# omaha_final.net
KiCad netlist of a schematic drawn in EAGLE
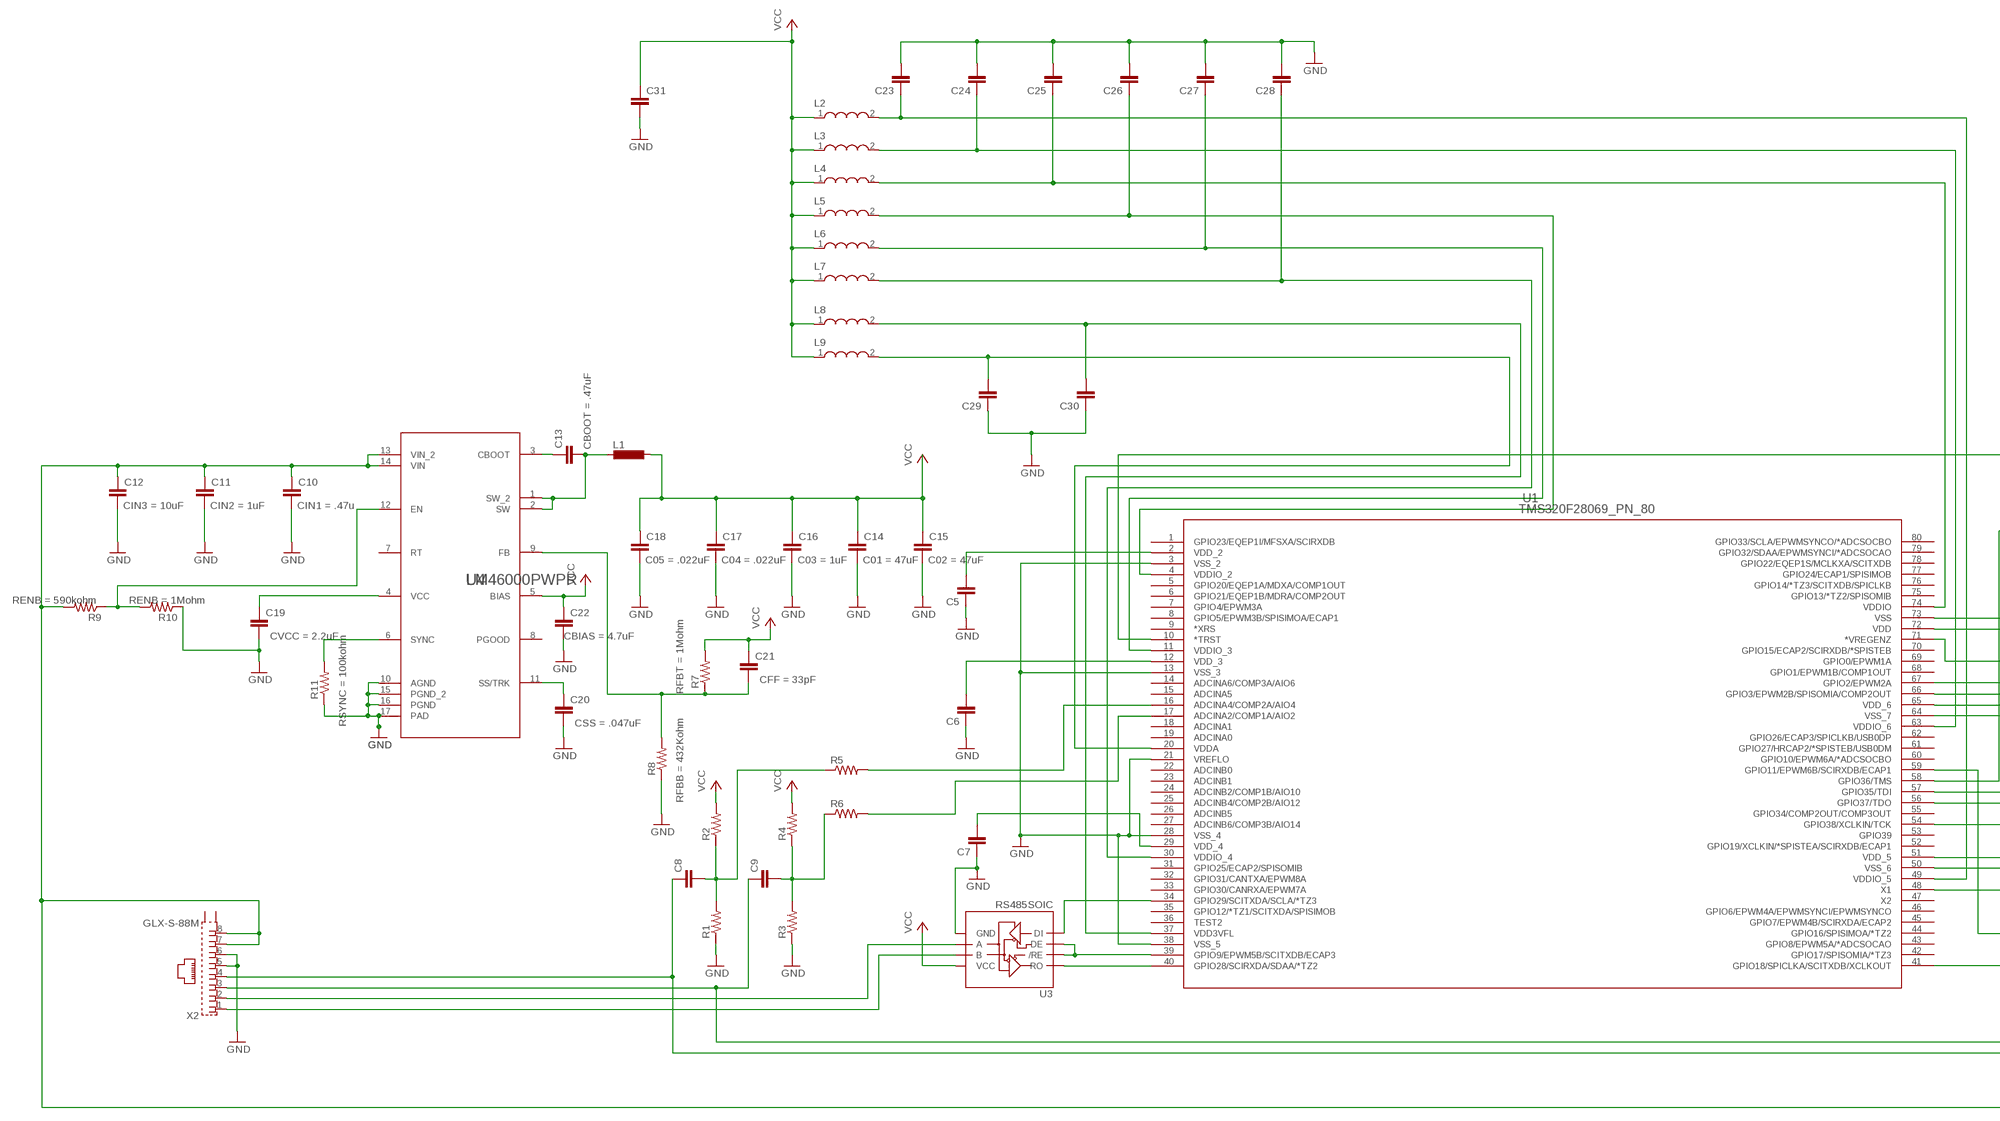
[diagram p0: schematic, sheet 1, part 1 of 2]
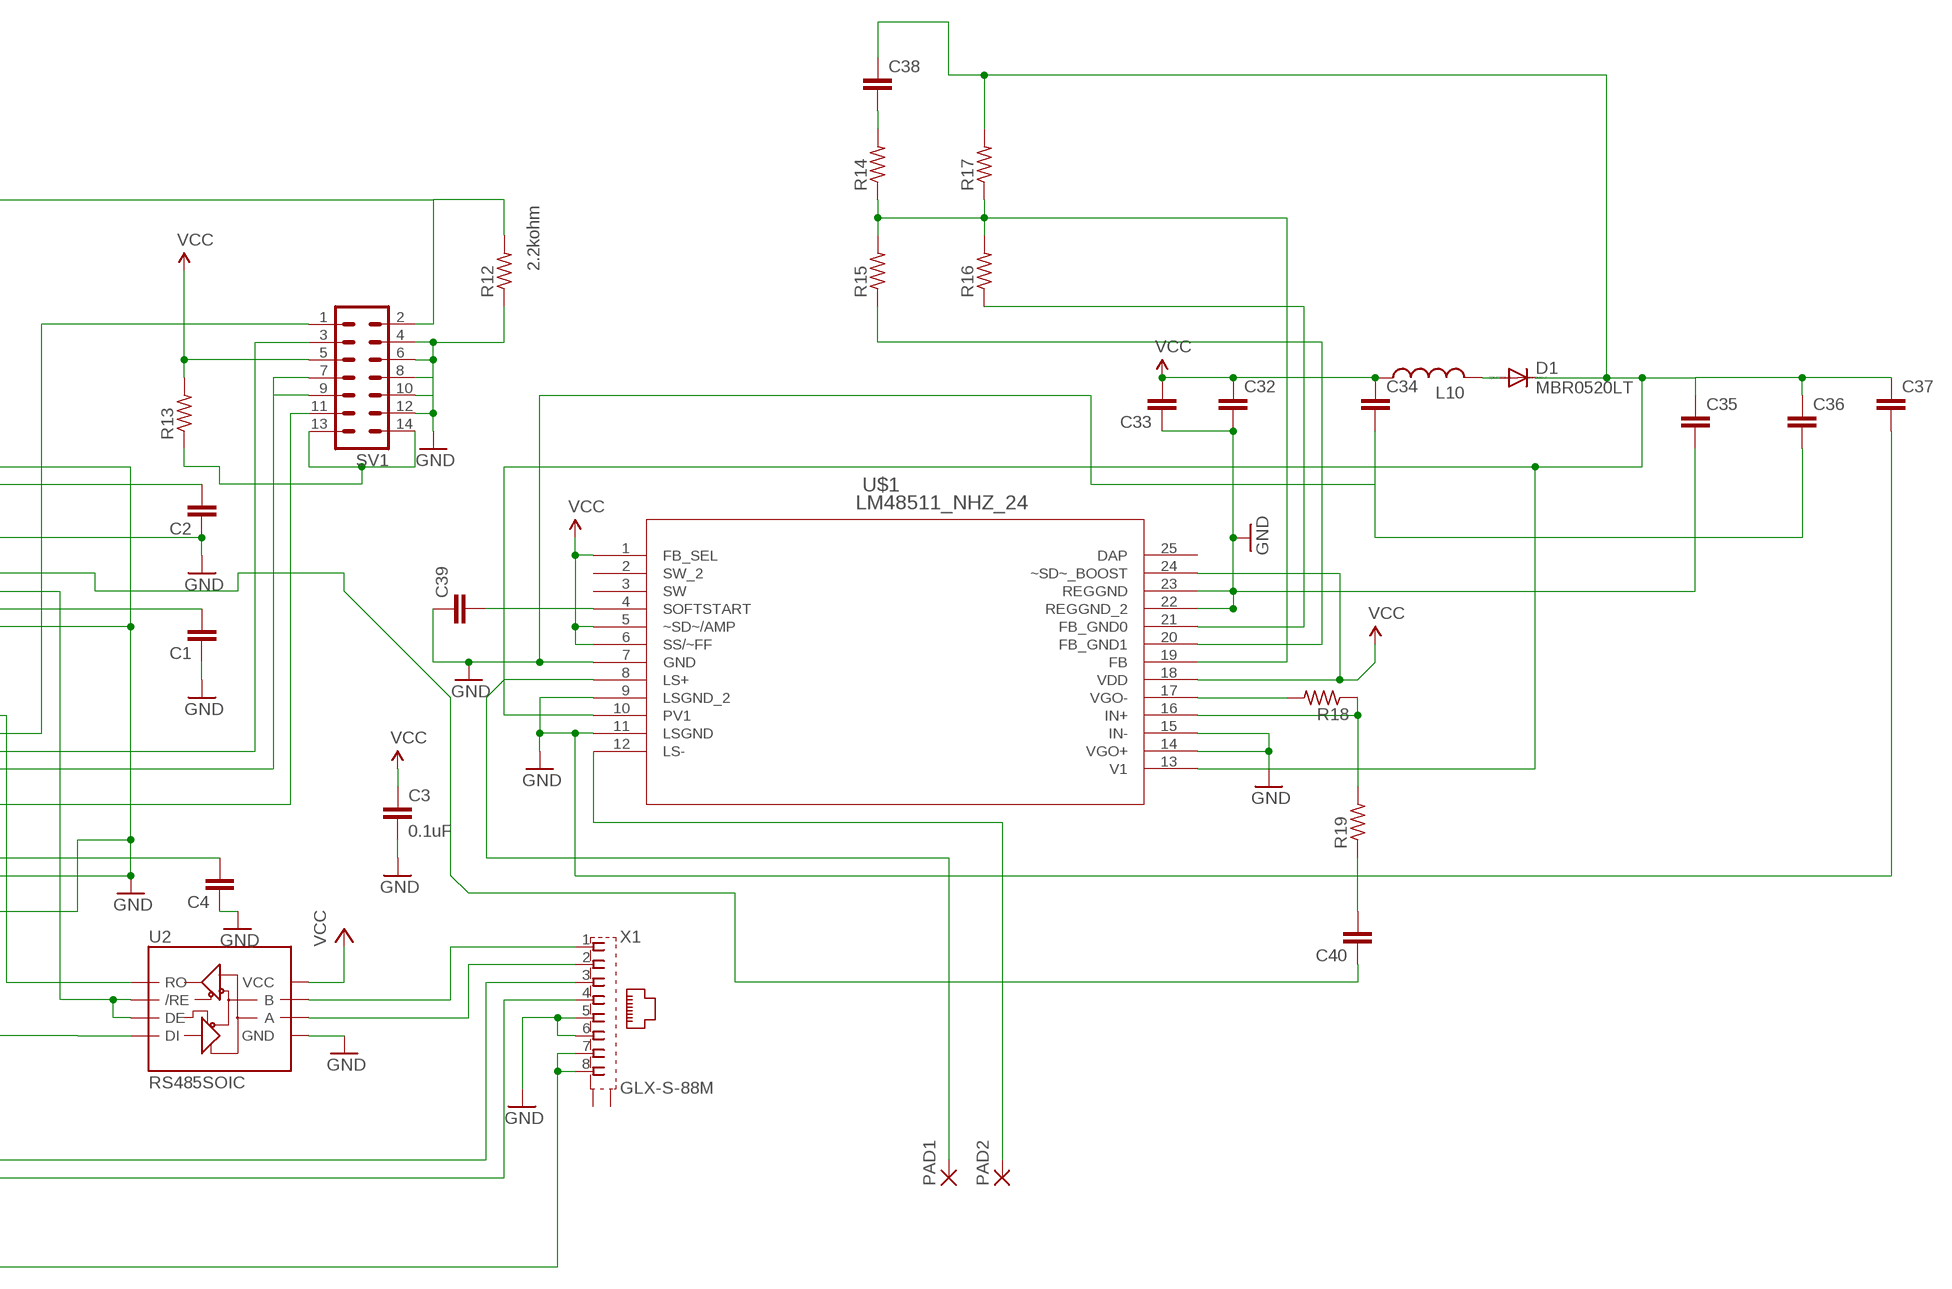
[diagram p1: schematic, sheet 1, part 2 of 2]

(export (version "E")
  (design (tool "Eeschema 10.0.6"))
  (components
    (comp (ref "C1")
      (value "C-EUC0603")
      (footprint "eagle-import:C0603")
      (libsource (lib "eagle-import") (part "C-EUC0603"))
    )
    (comp (ref "C2")
      (value "C-EUC0603")
      (footprint "eagle-import:C0603")
      (libsource (lib "eagle-import") (part "C-EUC0603"))
    )
    (comp (ref "C3")
      (value "0.1uF")
      (footprint "eagle-import:0603-CAP")
      (libsource (lib "eagle-import") (part "0.1UF-25V(+80/-20%)(0603)"))
    )
    (comp (ref "C4")
      (value "C-EUC0603")
      (footprint "eagle-import:C0603")
      (libsource (lib "eagle-import") (part "C-EUC0603"))
    )
    (comp (ref "C5")
      (value "C-EUC0603")
      (footprint "eagle-import:C0603")
      (libsource (lib "eagle-import") (part "C-EUC0603"))
    )
    (comp (ref "C6")
      (value "C-EUC0603")
      (footprint "eagle-import:C0603")
      (libsource (lib "eagle-import") (part "C-EUC0603"))
    )
    (comp (ref "C7")
      (value "C-EUC0603")
      (footprint "eagle-import:C0603")
      (libsource (lib "eagle-import") (part "C-EUC0603"))
    )
    (comp (ref "C8")
      (value "C-EUC0603")
      (footprint "eagle-import:C0603")
      (libsource (lib "eagle-import") (part "C-EUC0603"))
    )
    (comp (ref "C9")
      (value "C-EUC0603")
      (footprint "eagle-import:C0603")
      (libsource (lib "eagle-import") (part "C-EUC0603"))
    )
    (comp (ref "C10")
      (value "C-EUC0805")
      (footprint "eagle-import:C0805")
      (fields (field (name "CIN1") ".47u"))
      (libsource (lib "eagle-import") (part "C-EUC0805"))
    )
    (comp (ref "C11")
      (value "C-EUC1210")
      (footprint "eagle-import:C1210")
      (fields (field (name "CIN2") "1uF"))
      (libsource (lib "eagle-import") (part "C-EUC1210"))
    )
    (comp (ref "C12")
      (value "C-EUC2220K")
      (footprint "eagle-import:C2220K")
      (fields (field (name "CIN3") "10uF"))
      (libsource (lib "eagle-import") (part "C-EUC2220K"))
    )
    (comp (ref "C13")
      (value "C-EUC0805")
      (footprint "eagle-import:C0805")
      (fields (field (name "CBOOT") ".47uF"))
      (libsource (lib "eagle-import") (part "C-EUC0805"))
    )
    (comp (ref "C14")
      (value "C-EUC1210")
      (footprint "eagle-import:C1210")
      (fields (field (name "C01") "47uF"))
      (libsource (lib "eagle-import") (part "C-EUC1210"))
    )
    (comp (ref "C15")
      (value "C-EUC1210")
      (footprint "eagle-import:C1210")
      (fields (field (name "C02") "47uF"))
      (libsource (lib "eagle-import") (part "C-EUC1210"))
    )
    (comp (ref "C16")
      (value "C-EUC0805")
      (footprint "eagle-import:C0805")
      (fields (field (name "C03") "1uF"))
      (libsource (lib "eagle-import") (part "C-EUC0805"))
    )
    (comp (ref "C17")
      (value "C-EUC0805")
      (footprint "eagle-import:C0805")
      (fields (field (name "C04") ".022uF"))
      (libsource (lib "eagle-import") (part "C-EUC0805"))
    )
    (comp (ref "C18")
      (value "C-EUC0805")
      (footprint "eagle-import:C0805")
      (fields (field (name "C05") ".022uF"))
      (libsource (lib "eagle-import") (part "C-EUC0805"))
    )
    (comp (ref "C19")
      (value "C-EUC0603")
      (footprint "eagle-import:C0603")
      (fields (field (name "CVCC") "2.2uF"))
      (libsource (lib "eagle-import") (part "C-EUC0603"))
    )
    (comp (ref "C20")
      (value "C-EUC0603")
      (footprint "eagle-import:C0603")
      (fields (field (name "CSS") ".047uF"))
      (libsource (lib "eagle-import") (part "C-EUC0603"))
    )
    (comp (ref "C21")
      (value "C-EUC0603")
      (footprint "eagle-import:C0603")
      (fields (field (name "CFF") "33pF"))
      (libsource (lib "eagle-import") (part "C-EUC0603"))
    )
    (comp (ref "C22")
      (value "C-EUC0805")
      (footprint "eagle-import:C0805")
      (fields (field (name "CBIAS") "4.7uF"))
      (libsource (lib "eagle-import") (part "C-EUC0805"))
    )
    (comp (ref "C23")
      (value "C-EUC0603")
      (footprint "eagle-import:C0603")
      (libsource (lib "eagle-import") (part "C-EUC0603"))
    )
    (comp (ref "C24")
      (value "C-EUC0603")
      (footprint "eagle-import:C0603")
      (libsource (lib "eagle-import") (part "C-EUC0603"))
    )
    (comp (ref "C25")
      (value "C-EUC0603")
      (footprint "eagle-import:C0603")
      (libsource (lib "eagle-import") (part "C-EUC0603"))
    )
    (comp (ref "C26")
      (value "C-EUC0603")
      (footprint "eagle-import:C0603")
      (libsource (lib "eagle-import") (part "C-EUC0603"))
    )
    (comp (ref "C27")
      (value "C-EUC0603")
      (footprint "eagle-import:C0603")
      (libsource (lib "eagle-import") (part "C-EUC0603"))
    )
    (comp (ref "C28")
      (value "C-EUC0603")
      (footprint "eagle-import:C0603")
      (libsource (lib "eagle-import") (part "C-EUC0603"))
    )
    (comp (ref "C29")
      (value "C-EUC0603")
      (footprint "eagle-import:C0603")
      (libsource (lib "eagle-import") (part "C-EUC0603"))
    )
    (comp (ref "C30")
      (value "C-EUC0603")
      (footprint "eagle-import:C0603")
      (libsource (lib "eagle-import") (part "C-EUC0603"))
    )
    (comp (ref "C31")
      (value "C-EUC0603")
      (footprint "eagle-import:C0603")
      (libsource (lib "eagle-import") (part "C-EUC0603"))
    )
    (comp (ref "C32")
      (value "C-EUC0805")
      (footprint "eagle-import:C0805")
      (libsource (lib "eagle-import") (part "C-EUC0805"))
    )
    (comp (ref "C33")
      (value "C-EUC0805")
      (footprint "eagle-import:C0805")
      (libsource (lib "eagle-import") (part "C-EUC0805"))
    )
    (comp (ref "C34")
      (value "C-EUC0805")
      (footprint "eagle-import:C0805")
      (libsource (lib "eagle-import") (part "C-EUC0805"))
    )
    (comp (ref "C35")
      (value "C-EUC0805")
      (footprint "eagle-import:C0805")
      (libsource (lib "eagle-import") (part "C-EUC0805"))
    )
    (comp (ref "C36")
      (value "C-EUC0805")
      (footprint "eagle-import:C0805")
      (libsource (lib "eagle-import") (part "C-EUC0805"))
    )
    (comp (ref "C37")
      (value "C-EUC0805")
      (footprint "eagle-import:C0805")
      (libsource (lib "eagle-import") (part "C-EUC0805"))
    )
    (comp (ref "C38")
      (value "C-EUC0805")
      (footprint "eagle-import:C0805")
      (libsource (lib "eagle-import") (part "C-EUC0805"))
    )
    (comp (ref "C39")
      (value "C-EUC0805")
      (footprint "eagle-import:C0805")
      (libsource (lib "eagle-import") (part "C-EUC0805"))
    )
    (comp (ref "C40")
      (value "C-EUC0805")
      (footprint "eagle-import:C0805")
      (libsource (lib "eagle-import") (part "C-EUC0805"))
    )
    (comp (ref "D1")
      (value "MBR0520LT")
      (footprint "eagle-import:SOD123")
      (libsource (lib "eagle-import") (part "MBR0520LT"))
    )
    (comp (ref "L1")
      (value "DO3316P")
      (footprint "eagle-import:DO3316P")
      (libsource (lib "eagle-import") (part "DO3316P"))
    )
    (comp (ref "L2")
      (value "WE-KI_0805A")
      (footprint "eagle-import:WE-KI_0805A")
      (libsource (lib "eagle-import") (part "WE-KI_0805A"))
    )
    (comp (ref "L3")
      (value "WE-KI_0805A")
      (footprint "eagle-import:WE-KI_0805A")
      (libsource (lib "eagle-import") (part "WE-KI_0805A"))
    )
    (comp (ref "L4")
      (value "WE-KI_0805A")
      (footprint "eagle-import:WE-KI_0805A")
      (libsource (lib "eagle-import") (part "WE-KI_0805A"))
    )
    (comp (ref "L5")
      (value "WE-KI_0805A")
      (footprint "eagle-import:WE-KI_0805A")
      (libsource (lib "eagle-import") (part "WE-KI_0805A"))
    )
    (comp (ref "L6")
      (value "WE-KI_0805A")
      (footprint "eagle-import:WE-KI_0805A")
      (libsource (lib "eagle-import") (part "WE-KI_0805A"))
    )
    (comp (ref "L7")
      (value "WE-KI_0805A")
      (footprint "eagle-import:WE-KI_0805A")
      (libsource (lib "eagle-import") (part "WE-KI_0805A"))
    )
    (comp (ref "L8")
      (value "WE-KI_0805A")
      (footprint "eagle-import:WE-KI_0805A")
      (libsource (lib "eagle-import") (part "WE-KI_0805A"))
    )
    (comp (ref "L9")
      (value "WE-KI_0805A")
      (footprint "eagle-import:WE-KI_0805A")
      (libsource (lib "eagle-import") (part "WE-KI_0805A"))
    )
    (comp (ref "L10")
      (value "L-USL5650M")
      (footprint "eagle-import:L5650M")
      (libsource (lib "eagle-import") (part "L-USL5650M"))
    )
    (comp (ref "PAD1")
      (value "3,81/1,4")
      (footprint "eagle-import:3,81_1,4")
      (libsource (lib "eagle-import") (part "3,81/1,4"))
    )
    (comp (ref "PAD2")
      (value "3,81/1,4")
      (footprint "eagle-import:3,81_1,4")
      (libsource (lib "eagle-import") (part "3,81/1,4"))
    )
    (comp (ref "R1")
      (value "R-US_R0603")
      (footprint "eagle-import:R0603")
      (libsource (lib "eagle-import") (part "R-US_R0603"))
    )
    (comp (ref "R2")
      (value "R-US_R0603")
      (footprint "eagle-import:R0603")
      (libsource (lib "eagle-import") (part "R-US_R0603"))
    )
    (comp (ref "R3")
      (value "R-US_R0603")
      (footprint "eagle-import:R0603")
      (libsource (lib "eagle-import") (part "R-US_R0603"))
    )
    (comp (ref "R4")
      (value "R-US_R0603")
      (footprint "eagle-import:R0603")
      (libsource (lib "eagle-import") (part "R-US_R0603"))
    )
    (comp (ref "R5")
      (value "R-US_R0603")
      (footprint "eagle-import:R0603")
      (libsource (lib "eagle-import") (part "R-US_R0603"))
    )
    (comp (ref "R6")
      (value "R-US_R0603")
      (footprint "eagle-import:R0603")
      (libsource (lib "eagle-import") (part "R-US_R0603"))
    )
    (comp (ref "R7")
      (value "R-US_R0603")
      (footprint "eagle-import:R0603")
      (fields (field (name "RFBT") "1Mohm"))
      (libsource (lib "eagle-import") (part "R-US_R0603"))
    )
    (comp (ref "R8")
      (value "R-US_R0603")
      (footprint "eagle-import:R0603")
      (fields (field (name "RFBB") "432Kohm"))
      (libsource (lib "eagle-import") (part "R-US_R0603"))
    )
    (comp (ref "R9")
      (value "R-US_R0603")
      (footprint "eagle-import:R0603")
      (fields (field (name "RENB") "590kohm"))
      (libsource (lib "eagle-import") (part "R-US_R0603"))
    )
    (comp (ref "R10")
      (value "R-US_R0603")
      (footprint "eagle-import:R0603")
      (fields (field (name "RENB") "1Mohm"))
      (libsource (lib "eagle-import") (part "R-US_R0603"))
    )
    (comp (ref "R11")
      (value "R-US_R0603")
      (footprint "eagle-import:R0603")
      (fields (field (name "RSYNC") "100kohm"))
      (libsource (lib "eagle-import") (part "R-US_R0603"))
    )
    (comp (ref "R12")
      (value "R-US_R0603")
      (footprint "eagle-import:R0603")
      (fields (field (name "R12") "2.2kohm"))
      (libsource (lib "eagle-import") (part "R-US_R0603"))
    )
    (comp (ref "R13")
      (value "R-US_R0603")
      (footprint "eagle-import:R0603")
      (libsource (lib "eagle-import") (part "R-US_R0603"))
    )
    (comp (ref "R14")
      (value "R-US_R0805")
      (footprint "eagle-import:R0805")
      (libsource (lib "eagle-import") (part "R-US_R0805"))
    )
    (comp (ref "R15")
      (value "R-US_R0805")
      (footprint "eagle-import:R0805")
      (libsource (lib "eagle-import") (part "R-US_R0805"))
    )
    (comp (ref "R16")
      (value "R-US_R0805")
      (footprint "eagle-import:R0805")
      (libsource (lib "eagle-import") (part "R-US_R0805"))
    )
    (comp (ref "R17")
      (value "R-US_R0805")
      (footprint "eagle-import:R0805")
      (libsource (lib "eagle-import") (part "R-US_R0805"))
    )
    (comp (ref "R18")
      (value "R-US_R0805")
      (footprint "eagle-import:R0805")
      (libsource (lib "eagle-import") (part "R-US_R0805"))
    )
    (comp (ref "R19")
      (value "R-US_R0805")
      (footprint "eagle-import:R0805")
      (libsource (lib "eagle-import") (part "R-US_R0805"))
    )
    (comp (ref "SV1")
      (value "MA07-2W")
      (footprint "eagle-import:MA07-2W")
      (libsource (lib "eagle-import") (part "MA07-2W"))
    )
    (comp (ref "U$1")
      (value "LM48511_NHZ_24")
      (footprint "eagle-import:SQA24B")
      (fields (field (name "MANUFACTURER_PART_NUMBER") "lm48511sqnopb"))
      (libsource (lib "eagle-import") (part "LM48511_NHZ_24"))
    )
    (comp (ref "U1")
      (value "TMS320F28069_PN_80")
      (footprint "eagle-import:PN80")
      (fields
        (field (name "GENERIC_PART_NUMBER") "TMS320F28069")
        (field (name "MANUFACTURER") "Texas Instruments")
        (field (name "MANUFACTURER_PART_NUMBER") "tms320f28069_pn_80")
      )
      (libsource (lib "eagle-import") (part "TMS320F28069_PN_80"))
    )
    (comp (ref "U2")
      (value "RS485SOIC")
      (footprint "eagle-import:SO08")
      (libsource (lib "eagle-import") (part "RS485SOIC"))
    )
    (comp (ref "U3")
      (value "RS485SOIC")
      (footprint "eagle-import:SO08")
      (libsource (lib "eagle-import") (part "RS485SOIC"))
    )
    (comp (ref "U4")
      (value "LM46000PWPR")
      (footprint "eagle-import:PWP0016F")
      (fields
        (field (name "MANUFACTURER") "Texas Instruments")
        (field (name "PARTNUMBER") "LM46000PWP")
        (field (name "APPROVEDBY") "Not shown in title block")
        (field (name "AUTHOR") "Not shown in title block")
        (field (name "CHECKEDBY") "Not shown in title block")
        (field (name "ENGINEER") "Not shown in title block")
        (field (name "MODIFIEDDATE") "Not shown in title block")
        (field (name "PUBLISHER") "Texas Instruments")
        (field (name "SYMBOLCREATOR") "x0208326")
      )
      (libsource (lib "eagle-import") (part "LM46000PWPR"))
    )
    (comp (ref "X1")
      (value "GLX-S-88M")
      (footprint "eagle-import:GLX-S-88M")
      (libsource (lib "eagle-import") (part "GLX-S-88M"))
    )
    (comp (ref "X2")
      (value "GLX-S-88M")
      (footprint "eagle-import:GLX-S-88M")
      (libsource (lib "eagle-import") (part "GLX-S-88M"))
    )
  )
  (nets
    (net (code "1") (name "/DAP") (class "Default")
      (node (ref "U$1") (pin "25") (pinfunction "DAP_25") (pintype "power_in"))
    )
    (net (code "2") (name "GND") (class "Default")
      (node (ref "C1") (pin "1") (pinfunction "1_1") (pintype "passive"))
      (node (ref "C10") (pin "2") (pinfunction "2_2") (pintype "passive"))
      (node (ref "C11") (pin "2") (pinfunction "2_2") (pintype "passive"))
      (node (ref "C12") (pin "2") (pinfunction "2_2") (pintype "passive"))
      (node (ref "C14") (pin "2") (pinfunction "2_2") (pintype "passive"))
      (node (ref "C15") (pin "2") (pinfunction "2_2") (pintype "passive"))
      (node (ref "C16") (pin "2") (pinfunction "2_2") (pintype "passive"))
      (node (ref "C17") (pin "2") (pinfunction "2_2") (pintype "passive"))
      (node (ref "C18") (pin "2") (pinfunction "2_2") (pintype "passive"))
      (node (ref "C19") (pin "2") (pinfunction "2_2") (pintype "passive"))
      (node (ref "C2") (pin "1") (pinfunction "1_1") (pintype "passive"))
      (node (ref "C20") (pin "2") (pinfunction "2_2") (pintype "passive"))
      (node (ref "C22") (pin "2") (pinfunction "2_2") (pintype "passive"))
      (node (ref "C23") (pin "2") (pinfunction "2_2") (pintype "passive"))
      (node (ref "C24") (pin "2") (pinfunction "2_2") (pintype "passive"))
      (node (ref "C25") (pin "2") (pinfunction "2_2") (pintype "passive"))
      (node (ref "C26") (pin "2") (pinfunction "2_2") (pintype "passive"))
      (node (ref "C27") (pin "2") (pinfunction "2_2") (pintype "passive"))
      (node (ref "C28") (pin "2") (pinfunction "2_2") (pintype "passive"))
      (node (ref "C29") (pin "1") (pinfunction "1_1") (pintype "passive"))
      (node (ref "C3") (pin "2") (pinfunction "2_2") (pintype "passive"))
      (node (ref "C30") (pin "1") (pinfunction "1_1") (pintype "passive"))
      (node (ref "C31") (pin "2") (pinfunction "2_2") (pintype "passive"))
      (node (ref "C32") (pin "2") (pinfunction "2_2") (pintype "passive"))
      (node (ref "C33") (pin "1") (pinfunction "1_1") (pintype "passive"))
      (node (ref "C34") (pin "2") (pinfunction "2_2") (pintype "passive"))
      (node (ref "C35") (pin "2") (pinfunction "2_2") (pintype "passive"))
      (node (ref "C36") (pin "2") (pinfunction "2_2") (pintype "passive"))
      (node (ref "C37") (pin "2") (pinfunction "2_2") (pintype "passive"))
      (node (ref "C39") (pin "1") (pinfunction "1_1") (pintype "passive"))
      (node (ref "C4") (pin "1") (pinfunction "1_1") (pintype "passive"))
      (node (ref "C5") (pin "1") (pinfunction "1_1") (pintype "passive"))
      (node (ref "C6") (pin "1") (pinfunction "1_1") (pintype "passive"))
      (node (ref "C7") (pin "1") (pinfunction "1_1") (pintype "passive"))
      (node (ref "R1") (pin "1") (pinfunction "1_1") (pintype "passive"))
      (node (ref "R10") (pin "1") (pinfunction "1_1") (pintype "passive"))
      (node (ref "R11") (pin "1") (pinfunction "1_1") (pintype "passive"))
      (node (ref "R12") (pin "1") (pinfunction "1_1") (pintype "passive"))
      (node (ref "R3") (pin "1") (pinfunction "1_1") (pintype "passive"))
      (node (ref "R8") (pin "1") (pinfunction "1_1") (pintype "passive"))
      (node (ref "SV1") (pin "10") (pinfunction "10_10") (pintype "passive"))
      (node (ref "SV1") (pin "12") (pinfunction "12_12") (pintype "passive"))
      (node (ref "SV1") (pin "4") (pinfunction "4_4") (pintype "passive"))
      (node (ref "SV1") (pin "6") (pinfunction "6_6") (pintype "passive"))
      (node (ref "SV1") (pin "8") (pinfunction "8_8") (pintype "passive"))
      (node (ref "U$1") (pin "11") (pinfunction "LSGND_11") (pintype "power_in"))
      (node (ref "U$1") (pin "14") (pinfunction "VGO+_14") (pintype "output"))
      (node (ref "U$1") (pin "15") (pinfunction "IN-_15") (pintype "input"))
      (node (ref "U$1") (pin "22") (pinfunction "REGGND_2_22") (pintype "power_in"))
      (node (ref "U$1") (pin "23") (pinfunction "REGGND_23") (pintype "power_in"))
      (node (ref "U$1") (pin "7") (pinfunction "GND_7") (pintype "power_in"))
      (node (ref "U$1") (pin "9") (pinfunction "LSGND_2_9") (pintype "power_in"))
      (node (ref "U1") (pin "13") (pinfunction "VSS_3_13") (pintype "power_in"))
      (node (ref "U1") (pin "21") (pinfunction "VREFLO_21") (pintype "passive"))
      (node (ref "U1") (pin "28") (pinfunction "VSS_4_28") (pintype "power_in"))
      (node (ref "U1") (pin "3") (pinfunction "VSS_2_3") (pintype "power_in"))
      (node (ref "U1") (pin "38") (pinfunction "VSS_5_38") (pintype "power_in"))
      (node (ref "U1") (pin "48") (pinfunction "X1_48") (pintype "input"))
      (node (ref "U1") (pin "50") (pinfunction "VSS_6_50") (pintype "power_in"))
      (node (ref "U1") (pin "64") (pinfunction "VSS_7_64") (pintype "power_in"))
      (node (ref "U1") (pin "71") (pinfunction "*VREGENZ_71") (pintype "input"))
      (node (ref "U1") (pin "73") (pinfunction "VSS_73") (pintype "power_in"))
      (node (ref "U2") (pin "5") (pinfunction "GND_5") (pintype "bidirectional"))
      (node (ref "U3") (pin "5") (pinfunction "GND_5") (pintype "bidirectional"))
      (node (ref "U4") (pin "10") (pinfunction "AGND_10") (pintype "power_in"))
      (node (ref "U4") (pin "15") (pinfunction "PGND_2_15") (pintype "power_in"))
      (node (ref "U4") (pin "16") (pinfunction "PGND_16") (pintype "power_in"))
      (node (ref "U4") (pin "17") (pinfunction "PAD_17") (pintype "power_in"))
      (node (ref "X1") (pin "5") (pinfunction "5_5") (pintype "passive"))
      (node (ref "X1") (pin "6") (pinfunction "6_6") (pintype "passive"))
      (node (ref "X2") (pin "5") (pinfunction "5_5") (pintype "passive"))
      (node (ref "X2") (pin "6") (pinfunction "6_6") (pintype "passive"))
    )
    (net (code "3") (name "Net-(C8-Pad1)") (class "Default")
      (node (ref "C8") (pin "1") (pinfunction "1_1") (pintype "passive"))
      (node (ref "X1") (pin "4") (pinfunction "4_4") (pintype "passive"))
      (node (ref "X2") (pin "4") (pinfunction "4_4") (pintype "passive"))
    )
    (net (code "4") (name "Net-(C8-Pad2)") (class "Default")
      (node (ref "C8") (pin "2") (pinfunction "2_2") (pintype "passive"))
      (node (ref "R1") (pin "2") (pinfunction "2_2") (pintype "passive"))
      (node (ref "R2") (pin "1") (pinfunction "1_1") (pintype "passive"))
      (node (ref "R5") (pin "1") (pinfunction "1_1") (pintype "passive"))
    )
    (net (code "5") (name "Net-(C9-Pad1)") (class "Default")
      (node (ref "C9") (pin "1") (pinfunction "1_1") (pintype "passive"))
      (node (ref "X1") (pin "3") (pinfunction "3_3") (pintype "passive"))
      (node (ref "X2") (pin "3") (pinfunction "3_3") (pintype "passive"))
    )
    (net (code "6") (name "Net-(C9-Pad2)") (class "Default")
      (node (ref "C9") (pin "2") (pinfunction "2_2") (pintype "passive"))
      (node (ref "R3") (pin "2") (pinfunction "2_2") (pintype "passive"))
      (node (ref "R4") (pin "1") (pinfunction "1_1") (pintype "passive"))
      (node (ref "R6") (pin "1") (pinfunction "1_1") (pintype "passive"))
    )
    (net (code "7") (name "Net-(C38-Pad2)") (class "Default")
      (node (ref "C38") (pin "2") (pinfunction "2_2") (pintype "passive"))
      (node (ref "R14") (pin "2") (pinfunction "2_2") (pintype "passive"))
    )
    (net (code "8") (name "Net-(C40-Pad2)") (class "Default")
      (node (ref "C40") (pin "2") (pinfunction "2_2") (pintype "passive"))
      (node (ref "R19") (pin "1") (pinfunction "1_1") (pintype "passive"))
    )
    (net (code "9") (name "Net-(D1-PadA)") (class "Default")
      (node (ref "D1") (pin "A") (pinfunction "A_A") (pintype "passive"))
      (node (ref "L10") (pin "2") (pinfunction "2_2") (pintype "passive"))
    )
    (net (code "10") (name "Net-(PAD1-P)") (class "Default")
      (node (ref "PAD1") (pin "1") (pinfunction "P_1") (pintype "passive"))
      (node (ref "U$1") (pin "8") (pinfunction "LS+_8") (pintype "output"))
    )
    (net (code "11") (name "Net-(PAD2-P)") (class "Default")
      (node (ref "PAD2") (pin "1") (pinfunction "P_1") (pintype "passive"))
      (node (ref "U$1") (pin "12") (pinfunction "LS-_12") (pintype "output"))
    )
    (net (code "12") (name "Net-(R13-Pad1)") (class "Default")
      (node (ref "R13") (pin "1") (pinfunction "1_1") (pintype "passive"))
      (node (ref "SV1") (pin "13") (pinfunction "13_13") (pintype "passive"))
      (node (ref "SV1") (pin "14") (pinfunction "14_14") (pintype "passive"))
    )
    (net (code "13") (name "Net-(U$1-FB)") (class "Default")
      (node (ref "R14") (pin "1") (pinfunction "1_1") (pintype "passive"))
      (node (ref "R15") (pin "2") (pinfunction "2_2") (pintype "passive"))
      (node (ref "R16") (pin "2") (pinfunction "2_2") (pintype "passive"))
      (node (ref "R17") (pin "1") (pinfunction "1_1") (pintype "passive"))
      (node (ref "U$1") (pin "19") (pinfunction "FB_19") (pintype "input"))
    )
    (net (code "14") (name "Net-(U$1-FB_GND0)") (class "Default")
      (node (ref "R16") (pin "1") (pinfunction "1_1") (pintype "passive"))
      (node (ref "U$1") (pin "21") (pinfunction "FB_GND0_21") (pintype "power_in"))
    )
    (net (code "15") (name "Net-(U$1-FB_GND1)") (class "Default")
      (node (ref "R15") (pin "1") (pinfunction "1_1") (pintype "passive"))
      (node (ref "U$1") (pin "20") (pinfunction "FB_GND1_20") (pintype "power_in"))
    )
    (net (code "16") (name "Net-(U$1-IN+)") (class "Default")
      (node (ref "R18") (pin "1") (pinfunction "1_1") (pintype "passive"))
      (node (ref "R19") (pin "2") (pinfunction "2_2") (pintype "passive"))
      (node (ref "U$1") (pin "16") (pinfunction "IN+_16") (pintype "input"))
    )
    (net (code "17") (name "Net-(U$1-PV1)") (class "Default")
      (node (ref "C35") (pin "1") (pinfunction "1_1") (pintype "passive"))
      (node (ref "C36") (pin "1") (pinfunction "1_1") (pintype "passive"))
      (node (ref "C37") (pin "1") (pinfunction "1_1") (pintype "passive"))
      (node (ref "C38") (pin "1") (pinfunction "1_1") (pintype "passive"))
      (node (ref "D1") (pin "C") (pinfunction "C_C") (pintype "passive"))
      (node (ref "R17") (pin "2") (pinfunction "2_2") (pintype "passive"))
      (node (ref "U$1") (pin "10") (pinfunction "PV1_10") (pintype "power_in"))
      (node (ref "U$1") (pin "13") (pinfunction "V1_13") (pintype "power_in"))
    )
    (net (code "18") (name "Net-(U$1-SOFTSTART)") (class "Default")
      (node (ref "C39") (pin "2") (pinfunction "2_2") (pintype "passive"))
      (node (ref "U$1") (pin "4") (pinfunction "SOFTSTART_4") (pintype "passive"))
    )
    (net (code "19") (name "Net-(U$1-VGO-)") (class "Default")
      (node (ref "R18") (pin "2") (pinfunction "2_2") (pintype "passive"))
      (node (ref "U$1") (pin "17") (pinfunction "VGO-_17") (pintype "output"))
    )
    (net (code "20") (name "Net-(U1-*TRST)") (class "Default")
      (node (ref "R12") (pin "2") (pinfunction "2_2") (pintype "passive"))
      (node (ref "SV1") (pin "2") (pinfunction "2_2") (pintype "passive"))
      (node (ref "U1") (pin "10") (pinfunction "*TRST_10") (pintype "input"))
    )
    (net (code "21") (name "Net-(U1-ADCINA2{slash}COMP1A{slash}AIO2)") (class "Default")
      (node (ref "R6") (pin "2") (pinfunction "2_2") (pintype "passive"))
      (node (ref "U1") (pin "17") (pinfunction "ADCINA2/COMP1A/AIO2_17") (pintype "bidirectional"))
    )
    (net (code "22") (name "Net-(U1-ADCINA4{slash}COMP2A{slash}AIO4)") (class "Default")
      (node (ref "R5") (pin "2") (pinfunction "2_2") (pintype "passive"))
      (node (ref "U1") (pin "16") (pinfunction "ADCINA4/COMP2A/AIO4_16") (pintype "bidirectional"))
    )
    (net (code "23") (name "Net-(U1-GPIO2{slash}EPWM2A)") (class "Default")
      (node (ref "C40") (pin "1") (pinfunction "1_1") (pintype "passive"))
      (node (ref "U1") (pin "67") (pinfunction "GPIO2/EPWM2A_67") (pintype "bidirectional"))
    )
    (net (code "24") (name "Net-(U1-GPIO3{slash}EPWM2B{slash}SPISOMIA{slash}COMP2OUT)") (class "Default")
      (node (ref "U1") (pin "66") (pinfunction "GPIO3/EPWM2B/SPISOMIA/COMP2OUT_66") (pintype "bidirectional"))
      (node (ref "U2") (pin "2") (pinfunction "/RE_2") (pintype "bidirectional"))
      (node (ref "U2") (pin "3") (pinfunction "DE_3") (pintype "bidirectional"))
    )
    (net (code "25") (name "Net-(U1-GPIO9{slash}EPWM5B{slash}SCITXDB{slash}ECAP3)") (class "Default")
      (node (ref "U1") (pin "39") (pinfunction "GPIO9/EPWM5B/SCITXDB/ECAP3_39") (pintype "bidirectional"))
      (node (ref "U3") (pin "2") (pinfunction "/RE_2") (pintype "bidirectional"))
      (node (ref "U3") (pin "3") (pinfunction "DE_3") (pintype "bidirectional"))
    )
    (net (code "26") (name "Net-(U1-GPIO11{slash}EPWM6B{slash}SCIRXDB{slash}ECAP1)") (class "Default")
      (node (ref "U1") (pin "59") (pinfunction "GPIO11/EPWM6B/SCIRXDB/ECAP1_59") (pintype "bidirectional"))
      (node (ref "U2") (pin "1") (pinfunction "RO_1") (pintype "bidirectional"))
    )
    (net (code "27") (name "Net-(U1-GPIO18{slash}SPICLKA{slash}SCITXDB{slash}XCLKOUT)") (class "Default")
      (node (ref "U1") (pin "41") (pinfunction "GPIO18/SPICLKA/SCITXDB/XCLKOUT_41") (pintype "bidirectional"))
      (node (ref "U2") (pin "4") (pinfunction "DI_4") (pintype "bidirectional"))
    )
    (net (code "28") (name "Net-(U1-GPIO28{slash}SCIRXDA{slash}SDAA{slash}*TZ2)") (class "Default")
      (node (ref "U1") (pin "40") (pinfunction "GPIO28/SCIRXDA/SDAA/*TZ2_40") (pintype "bidirectional"))
      (node (ref "U3") (pin "1") (pinfunction "RO_1") (pintype "bidirectional"))
    )
    (net (code "29") (name "Net-(U1-GPIO29{slash}SCITXDA{slash}SCLA{slash}*TZ3)") (class "Default")
      (node (ref "U1") (pin "34") (pinfunction "GPIO29/SCITXDA/SCLA/*TZ3_34") (pintype "bidirectional"))
      (node (ref "U3") (pin "4") (pinfunction "DI_4") (pintype "bidirectional"))
    )
    (net (code "30") (name "Net-(U1-GPIO35{slash}TDI)") (class "Default")
      (node (ref "SV1") (pin "3") (pinfunction "3_3") (pintype "passive"))
      (node (ref "U1") (pin "57") (pinfunction "GPIO35/TDI_57") (pintype "bidirectional"))
    )
    (net (code "31") (name "Net-(U1-GPIO36{slash}TMS)") (class "Default")
      (node (ref "SV1") (pin "1") (pinfunction "1_1") (pintype "passive"))
      (node (ref "U1") (pin "58") (pinfunction "GPIO36/TMS_58") (pintype "bidirectional"))
    )
    (net (code "32") (name "Net-(U1-GPIO37{slash}TDO)") (class "Default")
      (node (ref "SV1") (pin "7") (pinfunction "7_7") (pintype "passive"))
      (node (ref "SV1") (pin "9") (pinfunction "9_9") (pintype "passive"))
      (node (ref "U1") (pin "56") (pinfunction "GPIO37/TDO_56") (pintype "bidirectional"))
    )
    (net (code "33") (name "Net-(U1-GPIO38{slash}XCLKIN{slash}TCK)") (class "Default")
      (node (ref "SV1") (pin "11") (pinfunction "11_11") (pintype "passive"))
      (node (ref "U1") (pin "54") (pinfunction "GPIO38/XCLKIN/TCK_54") (pintype "bidirectional"))
    )
    (net (code "34") (name "Net-(U1-VDD)") (class "Default")
      (node (ref "C2") (pin "2") (pinfunction "2_2") (pintype "passive"))
      (node (ref "U1") (pin "72") (pinfunction "VDD_72") (pintype "power_in"))
    )
    (net (code "35") (name "Net-(U1-VDD3VFL)") (class "Default")
      (node (ref "C30") (pin "2") (pinfunction "2_2") (pintype "passive"))
      (node (ref "L8") (pin "2") (pinfunction "2_2") (pintype "passive"))
      (node (ref "U1") (pin "37") (pinfunction "VDD3VFL_37") (pintype "power_in"))
    )
    (net (code "36") (name "Net-(U1-VDDA)") (class "Default")
      (node (ref "C29") (pin "2") (pinfunction "2_2") (pintype "passive"))
      (node (ref "L9") (pin "2") (pinfunction "2_2") (pintype "passive"))
      (node (ref "U1") (pin "20") (pinfunction "VDDA_20") (pintype "power_in"))
    )
    (net (code "37") (name "Net-(U1-VDDIO)") (class "Default")
      (node (ref "C25") (pin "1") (pinfunction "1_1") (pintype "passive"))
      (node (ref "L4") (pin "2") (pinfunction "2_2") (pintype "passive"))
      (node (ref "U1") (pin "74") (pinfunction "VDDIO_74") (pintype "power_in"))
    )
    (net (code "38") (name "Net-(U1-VDDIO_2)") (class "Default")
      (node (ref "C26") (pin "1") (pinfunction "1_1") (pintype "passive"))
      (node (ref "L5") (pin "2") (pinfunction "2_2") (pintype "passive"))
      (node (ref "U1") (pin "4") (pinfunction "VDDIO_2_4") (pintype "power_in"))
    )
    (net (code "39") (name "Net-(U1-VDDIO_3)") (class "Default")
      (node (ref "C27") (pin "1") (pinfunction "1_1") (pintype "passive"))
      (node (ref "L6") (pin "2") (pinfunction "2_2") (pintype "passive"))
      (node (ref "U1") (pin "11") (pinfunction "VDDIO_3_11") (pintype "power_in"))
    )
    (net (code "40") (name "Net-(U1-VDDIO_4)") (class "Default")
      (node (ref "C28") (pin "1") (pinfunction "1_1") (pintype "passive"))
      (node (ref "L7") (pin "2") (pinfunction "2_2") (pintype "passive"))
      (node (ref "U1") (pin "30") (pinfunction "VDDIO_4_30") (pintype "power_in"))
    )
    (net (code "41") (name "Net-(U1-VDDIO_5)") (class "Default")
      (node (ref "C23") (pin "1") (pinfunction "1_1") (pintype "passive"))
      (node (ref "L2") (pin "2") (pinfunction "2_2") (pintype "passive"))
      (node (ref "U1") (pin "49") (pinfunction "VDDIO_5_49") (pintype "power_in"))
    )
    (net (code "42") (name "Net-(U1-VDDIO_6)") (class "Default")
      (node (ref "C24") (pin "1") (pinfunction "1_1") (pintype "passive"))
      (node (ref "L3") (pin "2") (pinfunction "2_2") (pintype "passive"))
      (node (ref "U1") (pin "63") (pinfunction "VDDIO_6_63") (pintype "power_in"))
    )
    (net (code "43") (name "Net-(U1-VDD_2)") (class "Default")
      (node (ref "C5") (pin "2") (pinfunction "2_2") (pintype "passive"))
      (node (ref "U1") (pin "2") (pinfunction "VDD_2_2") (pintype "power_in"))
    )
    (net (code "44") (name "Net-(U1-VDD_3)") (class "Default")
      (node (ref "C6") (pin "2") (pinfunction "2_2") (pintype "passive"))
      (node (ref "U1") (pin "12") (pinfunction "VDD_3_12") (pintype "power_in"))
    )
    (net (code "45") (name "Net-(U1-VDD_4)") (class "Default")
      (node (ref "C7") (pin "2") (pinfunction "2_2") (pintype "passive"))
      (node (ref "U1") (pin "29") (pinfunction "VDD_4_29") (pintype "power_in"))
    )
    (net (code "46") (name "Net-(U1-VDD_5)") (class "Default")
      (node (ref "C4") (pin "2") (pinfunction "2_2") (pintype "passive"))
      (node (ref "U1") (pin "51") (pinfunction "VDD_5_51") (pintype "power_in"))
    )
    (net (code "47") (name "Net-(U1-VDD_6)") (class "Default")
      (node (ref "C1") (pin "2") (pinfunction "2_2") (pintype "passive"))
      (node (ref "U1") (pin "65") (pinfunction "VDD_6_65") (pintype "power_in"))
    )
    (net (code "48") (name "Net-(U2-A)") (class "Default")
      (node (ref "U2") (pin "6") (pinfunction "A_6") (pintype "bidirectional"))
      (node (ref "X1") (pin "2") (pinfunction "2_2") (pintype "passive"))
    )
    (net (code "49") (name "Net-(U2-B)") (class "Default")
      (node (ref "U2") (pin "7") (pinfunction "B_7") (pintype "bidirectional"))
      (node (ref "X1") (pin "1") (pinfunction "1_1") (pintype "passive"))
    )
    (net (code "50") (name "Net-(U3-A)") (class "Default")
      (node (ref "U3") (pin "6") (pinfunction "A_6") (pintype "bidirectional"))
      (node (ref "X2") (pin "2") (pinfunction "2_2") (pintype "passive"))
    )
    (net (code "51") (name "Net-(U3-B)") (class "Default")
      (node (ref "U3") (pin "7") (pinfunction "B_7") (pintype "bidirectional"))
      (node (ref "X2") (pin "1") (pinfunction "1_1") (pintype "passive"))
    )
    (net (code "52") (name "Net-(U4-CBOOT)") (class "Default")
      (node (ref "C13") (pin "1") (pinfunction "1_1") (pintype "passive"))
      (node (ref "U4") (pin "3") (pinfunction "CBOOT_3") (pintype "input"))
    )
    (net (code "53") (name "Net-(U4-EN)") (class "Default")
      (node (ref "R10") (pin "2") (pinfunction "2_2") (pintype "passive"))
      (node (ref "R9") (pin "1") (pinfunction "1_1") (pintype "passive"))
      (node (ref "U4") (pin "12") (pinfunction "EN_12") (pintype "input"))
    )
    (net (code "54") (name "Net-(U4-FB)") (class "Default")
      (node (ref "C21") (pin "2") (pinfunction "2_2") (pintype "passive"))
      (node (ref "R7") (pin "1") (pinfunction "1_1") (pintype "passive"))
      (node (ref "R8") (pin "2") (pinfunction "2_2") (pintype "passive"))
      (node (ref "U4") (pin "9") (pinfunction "FB_9") (pintype "input"))
    )
    (net (code "55") (name "Net-(U4-SS{slash}TRK)") (class "Default")
      (node (ref "C20") (pin "1") (pinfunction "1_1") (pintype "passive"))
      (node (ref "U4") (pin "11") (pinfunction "SS/TRK_11") (pintype "input"))
    )
    (net (code "56") (name "Net-(U4-SW)") (class "Default")
      (node (ref "C13") (pin "2") (pinfunction "2_2") (pintype "passive"))
      (node (ref "L1") (pin "1") (pinfunction "1_1") (pintype "passive"))
      (node (ref "U4") (pin "1") (pinfunction "SW_2_1") (pintype "power_in"))
      (node (ref "U4") (pin "2") (pinfunction "SW_2") (pintype "power_in"))
    )
    (net (code "57") (name "Net-(U4-SYNC)") (class "Default")
      (node (ref "R11") (pin "2") (pinfunction "2_2") (pintype "passive"))
      (node (ref "U4") (pin "6") (pinfunction "SYNC_6") (pintype "input"))
    )
    (net (code "58") (name "Net-(U4-VCC)") (class "Default")
      (node (ref "C19") (pin "1") (pinfunction "1_1") (pintype "passive"))
      (node (ref "U4") (pin "4") (pinfunction "VCC_4") (pintype "power_in"))
    )
    (net (code "59") (name "Net-(U4-VIN)") (class "Default")
      (node (ref "C10") (pin "1") (pinfunction "1_1") (pintype "passive"))
      (node (ref "C11") (pin "1") (pinfunction "1_1") (pintype "passive"))
      (node (ref "C12") (pin "1") (pinfunction "1_1") (pintype "passive"))
      (node (ref "R9") (pin "2") (pinfunction "2_2") (pintype "passive"))
      (node (ref "U4") (pin "13") (pinfunction "VIN_2_13") (pintype "power_in"))
      (node (ref "U4") (pin "14") (pinfunction "VIN_14") (pintype "power_in"))
      (node (ref "X1") (pin "7") (pinfunction "7_7") (pintype "passive"))
      (node (ref "X1") (pin "8") (pinfunction "8_8") (pintype "passive"))
      (node (ref "X2") (pin "7") (pinfunction "7_7") (pintype "passive"))
      (node (ref "X2") (pin "8") (pinfunction "8_8") (pintype "passive"))
    )
    (net (code "60") (name "VCC") (class "Default")
      (node (ref "C14") (pin "1") (pinfunction "1_1") (pintype "passive"))
      (node (ref "C15") (pin "1") (pinfunction "1_1") (pintype "passive"))
      (node (ref "C16") (pin "1") (pinfunction "1_1") (pintype "passive"))
      (node (ref "C17") (pin "1") (pinfunction "1_1") (pintype "passive"))
      (node (ref "C18") (pin "1") (pinfunction "1_1") (pintype "passive"))
      (node (ref "C21") (pin "1") (pinfunction "1_1") (pintype "passive"))
      (node (ref "C22") (pin "1") (pinfunction "1_1") (pintype "passive"))
      (node (ref "C3") (pin "1") (pinfunction "1_1") (pintype "passive"))
      (node (ref "C31") (pin "1") (pinfunction "1_1") (pintype "passive"))
      (node (ref "C32") (pin "1") (pinfunction "1_1") (pintype "passive"))
      (node (ref "C33") (pin "2") (pinfunction "2_2") (pintype "passive"))
      (node (ref "C34") (pin "1") (pinfunction "1_1") (pintype "passive"))
      (node (ref "L1") (pin "2") (pinfunction "2_2") (pintype "passive"))
      (node (ref "L10") (pin "1") (pinfunction "1_1") (pintype "passive"))
      (node (ref "L2") (pin "1") (pinfunction "1_1") (pintype "passive"))
      (node (ref "L3") (pin "1") (pinfunction "1_1") (pintype "passive"))
      (node (ref "L4") (pin "1") (pinfunction "1_1") (pintype "passive"))
      (node (ref "L5") (pin "1") (pinfunction "1_1") (pintype "passive"))
      (node (ref "L6") (pin "1") (pinfunction "1_1") (pintype "passive"))
      (node (ref "L7") (pin "1") (pinfunction "1_1") (pintype "passive"))
      (node (ref "L8") (pin "1") (pinfunction "1_1") (pintype "passive"))
      (node (ref "L9") (pin "1") (pinfunction "1_1") (pintype "passive"))
      (node (ref "R13") (pin "2") (pinfunction "2_2") (pintype "passive"))
      (node (ref "R2") (pin "2") (pinfunction "2_2") (pintype "passive"))
      (node (ref "R4") (pin "2") (pinfunction "2_2") (pintype "passive"))
      (node (ref "R7") (pin "2") (pinfunction "2_2") (pintype "passive"))
      (node (ref "SV1") (pin "5") (pinfunction "5_5") (pintype "passive"))
      (node (ref "U$1") (pin "1") (pinfunction "FB_SEL_1") (pintype "input"))
      (node (ref "U$1") (pin "18") (pinfunction "VDD_18") (pintype "power_in"))
      (node (ref "U$1") (pin "24") (pinfunction "~{SD}_BOOST_24") (pintype "input"))
      (node (ref "U$1") (pin "5") (pinfunction "~{SD}/AMP_5") (pintype "input"))
      (node (ref "U$1") (pin "6") (pinfunction "SS/~{FF}_6") (pintype "input"))
      (node (ref "U2") (pin "8") (pinfunction "VCC_8") (pintype "bidirectional"))
      (node (ref "U3") (pin "8") (pinfunction "VCC_8") (pintype "bidirectional"))
      (node (ref "U4") (pin "5") (pinfunction "BIAS_5") (pintype "power_in"))
    )
    (net (code "61") (name "unconnected-(U$1-SW-Pad3)") (class "Default")
      (node (ref "U$1") (pin "3") (pinfunction "SW_3") (pintype "passive"))
    )
    (net (code "62") (name "unconnected-(U$1-SW_2-Pad2)") (class "Default")
      (node (ref "U$1") (pin "2") (pinfunction "SW_2_2") (pintype "passive"))
    )
    (net (code "63") (name "unconnected-(U1-*XRS-Pad9)") (class "Default")
      (node (ref "U1") (pin "9") (pinfunction "*XRS_9") (pintype "bidirectional"))
    )
    (net (code "64") (name "unconnected-(U1-ADCINA0-Pad19)") (class "Default")
      (node (ref "U1") (pin "19") (pinfunction "ADCINA0_19") (pintype "passive"))
    )
    (net (code "65") (name "unconnected-(U1-ADCINA1-Pad18)") (class "Default")
      (node (ref "U1") (pin "18") (pinfunction "ADCINA1_18") (pintype "input"))
    )
    (net (code "66") (name "unconnected-(U1-ADCINA5-Pad15)") (class "Default")
      (node (ref "U1") (pin "15") (pinfunction "ADCINA5_15") (pintype "input"))
    )
    (net (code "67") (name "unconnected-(U1-ADCINA6{slash}COMP3A{slash}AIO6-Pad14)") (class "Default")
      (node (ref "U1") (pin "14") (pinfunction "ADCINA6/COMP3A/AIO6_14") (pintype "bidirectional"))
    )
    (net (code "68") (name "unconnected-(U1-ADCINB0-Pad22)") (class "Default")
      (node (ref "U1") (pin "22") (pinfunction "ADCINB0_22") (pintype "input"))
    )
    (net (code "69") (name "unconnected-(U1-ADCINB1-Pad23)") (class "Default")
      (node (ref "U1") (pin "23") (pinfunction "ADCINB1_23") (pintype "input"))
    )
    (net (code "70") (name "unconnected-(U1-ADCINB2{slash}COMP1B{slash}AIO10-Pad24)") (class "Default")
      (node (ref "U1") (pin "24") (pinfunction "ADCINB2/COMP1B/AIO10_24") (pintype "bidirectional"))
    )
    (net (code "71") (name "unconnected-(U1-ADCINB4{slash}COMP2B{slash}AIO12-Pad25)") (class "Default")
      (node (ref "U1") (pin "25") (pinfunction "ADCINB4/COMP2B/AIO12_25") (pintype "bidirectional"))
    )
    (net (code "72") (name "unconnected-(U1-ADCINB5-Pad26)") (class "Default")
      (node (ref "U1") (pin "26") (pinfunction "ADCINB5_26") (pintype "input"))
    )
    (net (code "73") (name "unconnected-(U1-ADCINB6{slash}COMP3B{slash}AIO14-Pad27)") (class "Default")
      (node (ref "U1") (pin "27") (pinfunction "ADCINB6/COMP3B/AIO14_27") (pintype "bidirectional"))
    )
    (net (code "74") (name "unconnected-(U1-GPIO0{slash}EPWM1A-Pad69)") (class "Default")
      (node (ref "U1") (pin "69") (pinfunction "GPIO0/EPWM1A_69") (pintype "bidirectional"))
    )
    (net (code "75") (name "unconnected-(U1-GPIO1{slash}EPWM1B{slash}COMP1OUT-Pad68)") (class "Default")
      (node (ref "U1") (pin "68") (pinfunction "GPIO1/EPWM1B/COMP1OUT_68") (pintype "bidirectional"))
    )
    (net (code "76") (name "unconnected-(U1-GPIO4{slash}EPWM3A-Pad7)") (class "Default")
      (node (ref "U1") (pin "7") (pinfunction "GPIO4/EPWM3A_7") (pintype "bidirectional"))
    )
    (net (code "77") (name "unconnected-(U1-GPIO5{slash}EPWM3B{slash}SPISIMOA{slash}ECAP1-Pad8)") (class "Default")
      (node (ref "U1") (pin "8") (pinfunction "GPIO5/EPWM3B/SPISIMOA/ECAP1_8") (pintype "bidirectional"))
    )
    (net (code "78") (name "unconnected-(U1-GPIO6{slash}EPWM4A{slash}EPWMSYNCI{slash}EPWMSYNCO-Pad46)") (class "Default")
      (node (ref "U1") (pin "46") (pinfunction "GPIO6/EPWM4A/EPWMSYNCI/EPWMSYNCO_46") (pintype "bidirectional"))
    )
    (net (code "79") (name "unconnected-(U1-GPIO7{slash}EPWM4B{slash}SCIRXDA{slash}ECAP2-Pad45)") (class "Default")
      (node (ref "U1") (pin "45") (pinfunction "GPIO7/EPWM4B/SCIRXDA/ECAP2_45") (pintype "bidirectional"))
    )
    (net (code "80") (name "unconnected-(U1-GPIO8{slash}EPWM5A{slash}*ADCSOCAO-Pad43)") (class "Default")
      (node (ref "U1") (pin "43") (pinfunction "GPIO8/EPWM5A/*ADCSOCAO_43") (pintype "bidirectional"))
    )
    (net (code "81") (name "unconnected-(U1-GPIO10{slash}EPWM6A{slash}*ADCSOCBO-Pad60)") (class "Default")
      (node (ref "U1") (pin "60") (pinfunction "GPIO10/EPWM6A/*ADCSOCBO_60") (pintype "bidirectional"))
    )
    (net (code "82") (name "unconnected-(U1-GPIO12{slash}*TZ1{slash}SCITXDA{slash}SPISIMOB-Pad35)") (class "Default")
      (node (ref "U1") (pin "35") (pinfunction "GPIO12/*TZ1/SCITXDA/SPISIMOB_35") (pintype "bidirectional"))
    )
    (net (code "83") (name "unconnected-(U1-GPIO13{slash}*TZ2{slash}SPISOMIB-Pad75)") (class "Default")
      (node (ref "U1") (pin "75") (pinfunction "GPIO13/*TZ2/SPISOMIB_75") (pintype "bidirectional"))
    )
    (net (code "84") (name "unconnected-(U1-GPIO14{slash}*TZ3{slash}SCITXDB{slash}SPICLKB-Pad76)") (class "Default")
      (node (ref "U1") (pin "76") (pinfunction "GPIO14/*TZ3/SCITXDB/SPICLKB_76") (pintype "bidirectional"))
    )
    (net (code "85") (name "unconnected-(U1-GPIO15{slash}ECAP2{slash}SCIRXDB{slash}*SPISTEB-Pad70)") (class "Default")
      (node (ref "U1") (pin "70") (pinfunction "GPIO15/ECAP2/SCIRXDB/*SPISTEB_70") (pintype "bidirectional"))
    )
    (net (code "86") (name "unconnected-(U1-GPIO16{slash}SPISIMOA{slash}*TZ2-Pad44)") (class "Default")
      (node (ref "U1") (pin "44") (pinfunction "GPIO16/SPISIMOA/*TZ2_44") (pintype "bidirectional"))
    )
    (net (code "87") (name "unconnected-(U1-GPIO17{slash}SPISOMIA{slash}*TZ3-Pad42)") (class "Default")
      (node (ref "U1") (pin "42") (pinfunction "GPIO17/SPISOMIA/*TZ3_42") (pintype "bidirectional"))
    )
    (net (code "88") (name "unconnected-(U1-GPIO19{slash}XCLKIN{slash}*SPISTEA{slash}SCIRXDB{slash}ECAP1-Pad52)") (class "Default")
      (node (ref "U1") (pin "52") (pinfunction "GPIO19/XCLKIN/*SPISTEA/SCIRXDB/ECAP1_52") (pintype "bidirectional"))
    )
    (net (code "89") (name "unconnected-(U1-GPIO20{slash}EQEP1A{slash}MDXA{slash}COMP1OUT-Pad5)") (class "Default")
      (node (ref "U1") (pin "5") (pinfunction "GPIO20/EQEP1A/MDXA/COMP1OUT_5") (pintype "bidirectional"))
    )
    (net (code "90") (name "unconnected-(U1-GPIO21{slash}EQEP1B{slash}MDRA{slash}COMP2OUT-Pad6)") (class "Default")
      (node (ref "U1") (pin "6") (pinfunction "GPIO21/EQEP1B/MDRA/COMP2OUT_6") (pintype "bidirectional"))
    )
    (net (code "91") (name "unconnected-(U1-GPIO22{slash}EQEP1S{slash}MCLKXA{slash}SCITXDB-Pad78)") (class "Default")
      (node (ref "U1") (pin "78") (pinfunction "GPIO22/EQEP1S/MCLKXA/SCITXDB_78") (pintype "bidirectional"))
    )
    (net (code "92") (name "unconnected-(U1-GPIO23{slash}EQEP1I{slash}MFSXA{slash}SCIRXDB-Pad1)") (class "Default")
      (node (ref "U1") (pin "1") (pinfunction "GPIO23/EQEP1I/MFSXA/SCIRXDB_1") (pintype "bidirectional"))
    )
    (net (code "93") (name "unconnected-(U1-GPIO24{slash}ECAP1{slash}SPISIMOB-Pad77)") (class "Default")
      (node (ref "U1") (pin "77") (pinfunction "GPIO24/ECAP1/SPISIMOB_77") (pintype "bidirectional"))
    )
    (net (code "94") (name "unconnected-(U1-GPIO25{slash}ECAP2{slash}SPISOMIB-Pad31)") (class "Default")
      (node (ref "U1") (pin "31") (pinfunction "GPIO25/ECAP2/SPISOMIB_31") (pintype "bidirectional"))
    )
    (net (code "95") (name "unconnected-(U1-GPIO26{slash}ECAP3{slash}SPICLKB{slash}USB0DP-Pad62)") (class "Default")
      (node (ref "U1") (pin "62") (pinfunction "GPIO26/ECAP3/SPICLKB/USB0DP_62") (pintype "bidirectional"))
    )
    (net (code "96") (name "unconnected-(U1-GPIO27{slash}HRCAP2{slash}*SPISTEB{slash}USB0DM-Pad61)") (class "Default")
      (node (ref "U1") (pin "61") (pinfunction "GPIO27/HRCAP2/*SPISTEB/USB0DM_61") (pintype "bidirectional"))
    )
    (net (code "97") (name "unconnected-(U1-GPIO30{slash}CANRXA{slash}EPWM7A-Pad33)") (class "Default")
      (node (ref "U1") (pin "33") (pinfunction "GPIO30/CANRXA/EPWM7A_33") (pintype "bidirectional"))
    )
    (net (code "98") (name "unconnected-(U1-GPIO31{slash}CANTXA{slash}EPWM8A-Pad32)") (class "Default")
      (node (ref "U1") (pin "32") (pinfunction "GPIO31/CANTXA/EPWM8A_32") (pintype "bidirectional"))
    )
    (net (code "99") (name "unconnected-(U1-GPIO32{slash}SDAA{slash}EPWMSYNCI{slash}*ADCSOCAO-Pad79)") (class "Default")
      (node (ref "U1") (pin "79") (pinfunction "GPIO32/SDAA/EPWMSYNCI/*ADCSOCAO_79") (pintype "bidirectional"))
    )
    (net (code "100") (name "unconnected-(U1-GPIO33{slash}SCLA{slash}EPWMSYNCO{slash}*ADCSOCBO-Pad80)") (class "Default")
      (node (ref "U1") (pin "80") (pinfunction "GPIO33/SCLA/EPWMSYNCO/*ADCSOCBO_80") (pintype "bidirectional"))
    )
    (net (code "101") (name "unconnected-(U1-GPIO34{slash}COMP2OUT{slash}COMP3OUT-Pad55)") (class "Default")
      (node (ref "U1") (pin "55") (pinfunction "GPIO34/COMP2OUT/COMP3OUT_55") (pintype "bidirectional"))
    )
    (net (code "102") (name "unconnected-(U1-GPIO39-Pad53)") (class "Default")
      (node (ref "U1") (pin "53") (pinfunction "GPIO39_53") (pintype "bidirectional"))
    )
    (net (code "103") (name "unconnected-(U1-TEST2-Pad36)") (class "Default")
      (node (ref "U1") (pin "36") (pinfunction "TEST2_36") (pintype "bidirectional"))
    )
    (net (code "104") (name "unconnected-(U1-X2-Pad47)") (class "Default")
      (node (ref "U1") (pin "47") (pinfunction "X2_47") (pintype "output"))
    )
    (net (code "105") (name "unconnected-(U4-PGOOD-Pad8)") (class "Default")
      (node (ref "U4") (pin "8") (pinfunction "PGOOD_8") (pintype "output"))
    )
    (net (code "106") (name "unconnected-(U4-RT-Pad7)") (class "Default")
      (node (ref "U4") (pin "7") (pinfunction "RT_7") (pintype "input"))
    )
    (net (code "107") (name "unconnected-(X1-PadS1)") (class "Default")
      (node (ref "X1") (pin "S1") (pinfunction "S1_S1") (pintype "passive"))
    )
    (net (code "108") (name "unconnected-(X1-PadS2)") (class "Default")
      (node (ref "X1") (pin "S2") (pinfunction "S2_S2") (pintype "passive"))
    )
    (net (code "109") (name "unconnected-(X2-PadS1)") (class "Default")
      (node (ref "X2") (pin "S1") (pinfunction "S1_S1") (pintype "passive"))
    )
    (net (code "110") (name "unconnected-(X2-PadS2)") (class "Default")
      (node (ref "X2") (pin "S2") (pinfunction "S2_S2") (pintype "passive"))
    )
  )
)
